# SCH_Copy_of_car_SchDoc_2023-05-21.net
KiCad netlist of a schematic drawn in EasyEDA
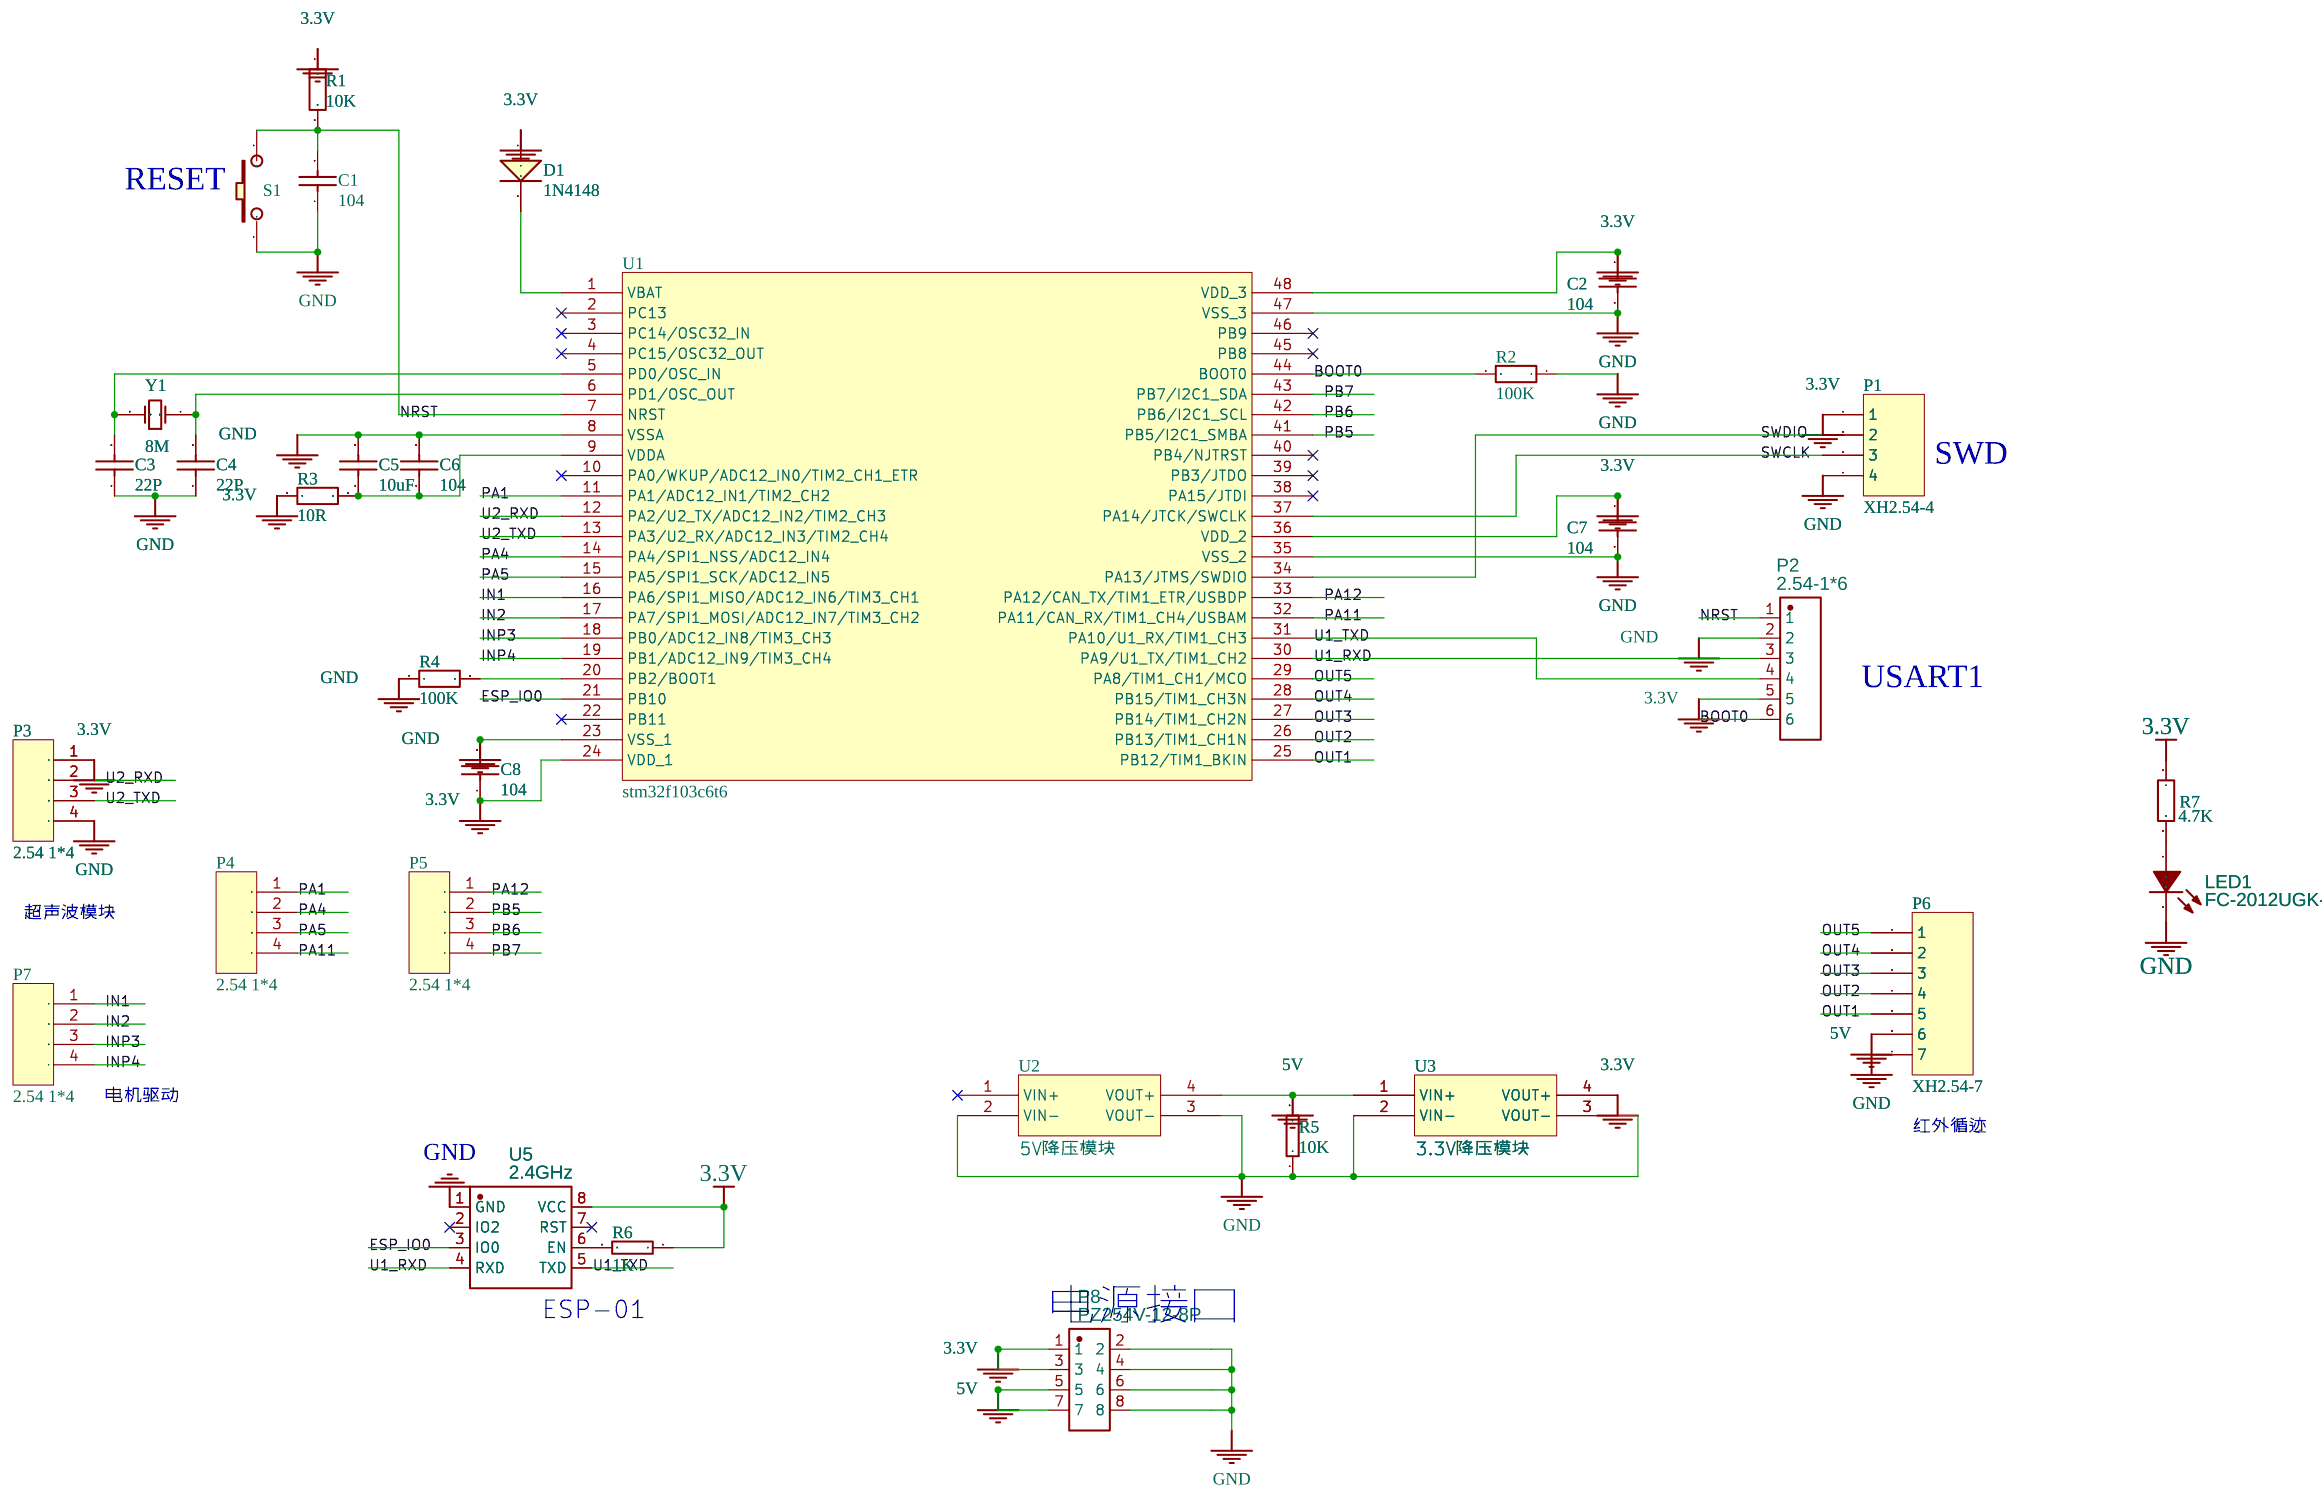
[diagram p0: schematic sheet]

(export (version "E")
  (design (tool "Eeschema 10.0.6"))
  (components
    (comp (ref "C1") (value "104") (libsource (lib "") (part "Unknown_210_-825")))
    (comp (ref "C2") (value "104") (libsource (lib "") (part "Unknown_830_-785")))
    (comp (ref "C3") (value "22P") (libsource (lib "") (part "Unknown_110_-685")))
    (comp (ref "C4") (value "22P") (libsource (lib "") (part "Unknown_150_-685")))
    (comp (ref "C5") (value "10uF") (libsource (lib "") (part "Unknown_230_-685")))
    (comp (ref "C6") (value "104") (libsource (lib "") (part "Unknown_260_-685")))
    (comp (ref "C7") (value "104") (libsource (lib "") (part "Unknown_830_-665")))
    (comp (ref "C8") (value "104") (libsource (lib "") (part "Unknown_290_-535")))
    (comp (ref "D1") (value "1N4148") (libsource (lib "") (part "Unknown_300_-815")))
    (comp (ref "LED1")
      (value "FC-2012UGK-520D5")
      (fields (field (name "BOM_Manufacturer Part") "NCD0805G1") (field (name "BOM_Supplier Part") "C84260"))
      (libsource (lib "") (part "FC-2012UGK-520D5"))
    )
    (comp (ref "P1") (value "XH2.54-4") (libsource (lib "") (part "Unknown_961_-725")))
    (comp (ref "P2")
      (value "2.54-1*6")
      (fields (field (name "BOM_Supplier Part") "C5156615"))
      (libsource (lib "") (part "2.54-1*6"))
    )
    (comp (ref "P3") (value "2.54 1*4") (libsource (lib "") (part "Unknown_50_-555")))
    (comp (ref "P4") (value "2.54 1*4") (libsource (lib "") (part "Unknown_150_-490")))
    (comp (ref "P5") (value "2.54 1*4") (libsource (lib "") (part "Unknown_245_-490")))
    (comp (ref "P6") (value "XH2.54-7") (libsource (lib "") (part "Unknown_985_-470")))
    (comp (ref "P7") (value "2.54 1*4") (libsource (lib "") (part "Unknown_50_-435")))
    (comp (ref "P8")
      (value "PZ254V-12-8P")
      (fields (field (name "BOM_Supplier Part") "C492421"))
      (libsource (lib "") (part "PZ254V-12-8P"))
    )
    (comp (ref "R1") (value "10K") (libsource (lib "") (part "Unknown_200_-855")))
    (comp (ref "R2") (value "100K") (libsource (lib "") (part "Unknown_800_-745")))
    (comp (ref "R3") (value "10R") (libsource (lib "") (part "Unknown_220_-675")))
    (comp (ref "R4") (value "100K") (libsource (lib "") (part "Unknown_250_-575")))
    (comp (ref "R5") (value "10K") (libsource (lib "") (part "Unknown_680_-380")))
    (comp (ref "R6") (value "1K") (libsource (lib "") (part "Unknown_335_-305")))
    (comp (ref "R7") (value "4.7K") (libsource (lib "") (part "Unknown_1100_-535")))
    (comp (ref "S1") (value "key") (libsource (lib "") (part "Unknown_170_-795")))
    (comp (ref "U1") (value "stm32f103c6t6") (libsource (lib "") (part "Unknown_350_-785")))
    (comp (ref "U2") (value "5V降压模块") (libsource (lib "") (part "Unknown_545_-390")))
    (comp (ref "U3") (value "3.3V降压模块") (libsource (lib "") (part "Unknown_740_-390")))
    (comp (ref "U5")
      (value "2.4GHz")
      (fields (field (name "BOM_Manufacturer Part") "ESP-01") (field (name "BOM_Supplier Part") "C503581"))
      (libsource (lib "") (part "ESP-01"))
    )
    (comp (ref "Y1") (value "8M") (libsource (lib "") (part "Unknown_100_-715")))
  )
  (nets
    (net (code "1") (name "/BOOT0") (class "Default")
      (node (ref "P2") (pin "6") (pinfunction "6_6") (pintype "unspecified"))
      (node (ref "R2") (pin "2") (pinfunction "2_2") (pintype "unspecified"))
      (node (ref "U1") (pin "44") (pinfunction "BOOT0_44") (pintype "unspecified"))
    )
    (net (code "2") (name "/ESP_IO0") (class "Default")
      (node (ref "U1") (pin "21") (pinfunction "PB10_21") (pintype "unspecified"))
      (node (ref "U5") (pin "3") (pinfunction "IO0_3") (pintype "unspecified"))
    )
    (net (code "3") (name "/IN1") (class "Default")
      (node (ref "P7") (pin "1") (pinfunction "1_1") (pintype "unspecified"))
      (node (ref "U1") (pin "16") (pinfunction "PA6/SPI1_MISO/ADC12_IN6/TIM3_CH1_16") (pintype "unspecified"))
    )
    (net (code "4") (name "/IN2") (class "Default")
      (node (ref "P7") (pin "2") (pinfunction "2_2") (pintype "unspecified"))
      (node (ref "U1") (pin "17") (pinfunction "PA7/SPI1_MOSI/ADC12_IN7/TIM3_CH2_17") (pintype "unspecified"))
    )
    (net (code "5") (name "/INP3") (class "Default")
      (node (ref "P7") (pin "3") (pinfunction "3_3") (pintype "unspecified"))
      (node (ref "U1") (pin "18") (pinfunction "PB0/ADC12_IN8/TIM3_CH3_18") (pintype "unspecified"))
    )
    (net (code "6") (name "/INP4") (class "Default")
      (node (ref "P7") (pin "4") (pinfunction "4_4") (pintype "unspecified"))
      (node (ref "U1") (pin "19") (pinfunction "PB1/ADC12_IN9/TIM3_CH4_19") (pintype "unspecified"))
    )
    (net (code "7") (name "/NRST") (class "Default")
      (node (ref "C1") (pin "2") (pintype "unspecified"))
      (node (ref "P2") (pin "1") (pinfunction "1_1") (pintype "unspecified"))
      (node (ref "R1") (pin "2") (pinfunction "2_2") (pintype "unspecified"))
      (node (ref "S1") (pin "2") (pinfunction "2_2") (pintype "unspecified"))
      (node (ref "U1") (pin "7") (pinfunction "NRST_7") (pintype "unspecified"))
    )
    (net (code "8") (name "/OUT1") (class "Default")
      (node (ref "P6") (pin "5") (pinfunction "5_5") (pintype "unspecified"))
      (node (ref "U1") (pin "25") (pinfunction "PB12/TIM1_BKIN_25") (pintype "unspecified"))
    )
    (net (code "9") (name "/OUT2") (class "Default")
      (node (ref "P6") (pin "4") (pinfunction "4_4") (pintype "unspecified"))
      (node (ref "U1") (pin "26") (pinfunction "PB13/TIM1_CH1N_26") (pintype "unspecified"))
    )
    (net (code "10") (name "/OUT3") (class "Default")
      (node (ref "P6") (pin "3") (pinfunction "3_3") (pintype "unspecified"))
      (node (ref "U1") (pin "27") (pinfunction "PB14/TIM1_CH2N_27") (pintype "unspecified"))
    )
    (net (code "11") (name "/OUT4") (class "Default")
      (node (ref "P6") (pin "2") (pinfunction "2_2") (pintype "unspecified"))
      (node (ref "U1") (pin "28") (pinfunction "PB15/TIM1_CH3N_28") (pintype "unspecified"))
    )
    (net (code "12") (name "/OUT5") (class "Default")
      (node (ref "P6") (pin "1") (pinfunction "1_1") (pintype "unspecified"))
      (node (ref "U1") (pin "29") (pinfunction "PA8/TIM1_CH1/MCO_29") (pintype "unspecified"))
    )
    (net (code "13") (name "/PA1") (class "Default")
      (node (ref "P4") (pin "1") (pinfunction "1_1") (pintype "unspecified"))
      (node (ref "U1") (pin "11") (pinfunction "PA1/ADC12_IN1/TIM2_CH2_11") (pintype "unspecified"))
    )
    (net (code "14") (name "/PA4") (class "Default")
      (node (ref "P4") (pin "2") (pinfunction "2_2") (pintype "unspecified"))
      (node (ref "U1") (pin "14") (pinfunction "PA4/SPI1_NSS/ADC12_IN4_14") (pintype "unspecified"))
    )
    (net (code "15") (name "/PA5") (class "Default")
      (node (ref "P4") (pin "3") (pinfunction "3_3") (pintype "unspecified"))
      (node (ref "U1") (pin "15") (pinfunction "PA5/SPI1_SCK/ADC12_IN5_15") (pintype "unspecified"))
    )
    (net (code "16") (name "/PA11") (class "Default")
      (node (ref "P4") (pin "4") (pinfunction "4_4") (pintype "unspecified"))
      (node (ref "U1") (pin "32") (pinfunction "PA11/CAN_RX/TIM1_CH4/USBAM_32") (pintype "unspecified"))
    )
    (net (code "17") (name "/PA12") (class "Default")
      (node (ref "P5") (pin "1") (pinfunction "1_1") (pintype "unspecified"))
      (node (ref "U1") (pin "33") (pinfunction "PA12/CAN_TX/TIM1_ETR/USBDP_33") (pintype "unspecified"))
    )
    (net (code "18") (name "/PB5") (class "Default")
      (node (ref "P5") (pin "2") (pinfunction "2_2") (pintype "unspecified"))
      (node (ref "U1") (pin "41") (pinfunction "PB5/I2C1_SMBA_41") (pintype "unspecified"))
    )
    (net (code "19") (name "/PB6") (class "Default")
      (node (ref "P5") (pin "3") (pinfunction "3_3") (pintype "unspecified"))
      (node (ref "U1") (pin "42") (pinfunction "PB6/I2C1_SCL_42") (pintype "unspecified"))
    )
    (net (code "20") (name "/PB7") (class "Default")
      (node (ref "P5") (pin "4") (pinfunction "4_4") (pintype "unspecified"))
      (node (ref "U1") (pin "43") (pinfunction "PB7/I2C1_SDA_43") (pintype "unspecified"))
    )
    (net (code "21") (name "/SWCLK") (class "Default")
      (node (ref "P1") (pin "3") (pinfunction "3_3") (pintype "unspecified"))
      (node (ref "U1") (pin "37") (pinfunction "PA14/JTCK/SWCLK_37") (pintype "unspecified"))
    )
    (net (code "22") (name "/SWDIO") (class "Default")
      (node (ref "P1") (pin "2") (pinfunction "2_2") (pintype "unspecified"))
      (node (ref "U1") (pin "34") (pinfunction "PA13/JTMS/SWDIO_34") (pintype "unspecified"))
    )
    (net (code "23") (name "/U1_RXD") (class "Default")
      (node (ref "P2") (pin "3") (pinfunction "3_3") (pintype "unspecified"))
      (node (ref "U1") (pin "30") (pinfunction "PA9/U1_TX/TIM1_CH2_30") (pintype "unspecified"))
      (node (ref "U5") (pin "4") (pinfunction "RXD_4") (pintype "unspecified"))
    )
    (net (code "24") (name "/U1_TXD") (class "Default")
      (node (ref "P2") (pin "4") (pinfunction "4_4") (pintype "unspecified"))
      (node (ref "U1") (pin "31") (pinfunction "PA10/U1_RX/TIM1_CH3_31") (pintype "unspecified"))
      (node (ref "U5") (pin "5") (pinfunction "TXD_5") (pintype "unspecified"))
    )
    (net (code "25") (name "/U2_RXD") (class "Default")
      (node (ref "P3") (pin "2") (pinfunction "2_2") (pintype "unspecified"))
      (node (ref "U1") (pin "12") (pinfunction "PA2/U2_TX/ADC12_IN2/TIM2_CH3_12") (pintype "unspecified"))
    )
    (net (code "26") (name "/U2_TXD") (class "Default")
      (node (ref "P3") (pin "3") (pinfunction "3_3") (pintype "unspecified"))
      (node (ref "U1") (pin "13") (pinfunction "PA3/U2_RX/ADC12_IN3/TIM2_CH4_13") (pintype "unspecified"))
    )
    (net (code "27") (name "3.3V") (class "Default")
      (node (ref "C2") (pin "1") (pintype "unspecified"))
      (node (ref "C7") (pin "1") (pintype "unspecified"))
      (node (ref "C8") (pin "1") (pintype "unspecified"))
      (node (ref "D1") (pin "1") (pinfunction "A_1") (pintype "unspecified"))
      (node (ref "P1") (pin "1") (pinfunction "1_1") (pintype "unspecified"))
      (node (ref "P2") (pin "5") (pinfunction "5_5") (pintype "unspecified"))
      (node (ref "P3") (pin "1") (pinfunction "1_1") (pintype "unspecified"))
      (node (ref "P8") (pin "1") (pinfunction "1_1") (pintype "unspecified"))
      (node (ref "P8") (pin "3") (pinfunction "3_3") (pintype "unspecified"))
      (node (ref "R1") (pin "1") (pinfunction "1_1") (pintype "unspecified"))
      (node (ref "R3") (pin "1") (pinfunction "1_1") (pintype "unspecified"))
      (node (ref "R6") (pin "1") (pinfunction "1_1") (pintype "unspecified"))
      (node (ref "R7") (pin "1") (pinfunction "1_1") (pintype "unspecified"))
      (node (ref "U1") (pin "24") (pinfunction "VDD_1_24") (pintype "unspecified"))
      (node (ref "U1") (pin "36") (pinfunction "VDD_2_36") (pintype "unspecified"))
      (node (ref "U1") (pin "48") (pinfunction "VDD_3_48") (pintype "unspecified"))
      (node (ref "U3") (pin "4") (pinfunction "VOUT+_4") (pintype "unspecified"))
      (node (ref "U5") (pin "8") (pinfunction "VCC_8") (pintype "unspecified"))
    )
    (net (code "28") (name "5V") (class "Default")
      (node (ref "P6") (pin "6") (pinfunction "6_6") (pintype "unspecified"))
      (node (ref "P8") (pin "5") (pinfunction "5_5") (pintype "unspecified"))
      (node (ref "P8") (pin "7") (pinfunction "7_7") (pintype "unspecified"))
      (node (ref "R5") (pin "2") (pinfunction "2_2") (pintype "unspecified"))
      (node (ref "U2") (pin "4") (pinfunction "VOUT+_4") (pintype "unspecified"))
      (node (ref "U3") (pin "1") (pinfunction "VIN+_1") (pintype "unspecified"))
    )
    (net (code "29") (name "GND") (class "Default")
      (node (ref "C1") (pin "1") (pintype "unspecified"))
      (node (ref "C2") (pin "2") (pintype "unspecified"))
      (node (ref "C3") (pin "1") (pintype "unspecified"))
      (node (ref "C4") (pin "1") (pintype "unspecified"))
      (node (ref "C5") (pin "2") (pintype "unspecified"))
      (node (ref "C6") (pin "2") (pintype "unspecified"))
      (node (ref "C7") (pin "2") (pintype "unspecified"))
      (node (ref "C8") (pin "2") (pintype "unspecified"))
      (node (ref "LED1") (pin "2") (pinfunction "K_2") (pintype "unspecified"))
      (node (ref "P1") (pin "4") (pinfunction "4_4") (pintype "unspecified"))
      (node (ref "P2") (pin "2") (pinfunction "2_2") (pintype "unspecified"))
      (node (ref "P3") (pin "4") (pinfunction "4_4") (pintype "unspecified"))
      (node (ref "P6") (pin "7") (pinfunction "7_7") (pintype "unspecified"))
      (node (ref "P8") (pin "2") (pinfunction "2_2") (pintype "unspecified"))
      (node (ref "P8") (pin "4") (pinfunction "4_4") (pintype "unspecified"))
      (node (ref "P8") (pin "6") (pinfunction "6_6") (pintype "unspecified"))
      (node (ref "P8") (pin "8") (pinfunction "8_8") (pintype "unspecified"))
      (node (ref "R2") (pin "1") (pinfunction "1_1") (pintype "unspecified"))
      (node (ref "R4") (pin "1") (pinfunction "1_1") (pintype "unspecified"))
      (node (ref "R5") (pin "1") (pinfunction "1_1") (pintype "unspecified"))
      (node (ref "S1") (pin "1") (pinfunction "1_1") (pintype "unspecified"))
      (node (ref "U1") (pin "23") (pinfunction "VSS_1_23") (pintype "unspecified"))
      (node (ref "U1") (pin "35") (pinfunction "VSS_2_35") (pintype "unspecified"))
      (node (ref "U1") (pin "47") (pinfunction "VSS_3_47") (pintype "unspecified"))
      (node (ref "U1") (pin "8") (pinfunction "VSSA_8") (pintype "unspecified"))
      (node (ref "U2") (pin "2") (pinfunction "VIN-_2") (pintype "unspecified"))
      (node (ref "U2") (pin "3") (pinfunction "VOUT-_3") (pintype "unspecified"))
      (node (ref "U3") (pin "2") (pinfunction "VIN-_2") (pintype "unspecified"))
      (node (ref "U3") (pin "3") (pinfunction "VOUT-_3") (pintype "unspecified"))
      (node (ref "U5") (pin "1") (pinfunction "GND_1") (pintype "unspecified"))
    )
    (net (code "30") (name "Net-(D1-K)") (class "Default")
      (node (ref "D1") (pin "2") (pinfunction "K_2") (pintype "unspecified"))
      (node (ref "U1") (pin "1") (pinfunction "VBAT_1") (pintype "unspecified"))
    )
    (net (code "31") (name "Net-(LED1-A)") (class "Default")
      (node (ref "LED1") (pin "1") (pinfunction "A_1") (pintype "unspecified"))
      (node (ref "R7") (pin "2") (pinfunction "2_2") (pintype "unspecified"))
    )
    (net (code "32") (name "Net-(U1-PB2{slash}BOOT1)") (class "Default")
      (node (ref "R4") (pin "2") (pinfunction "2_2") (pintype "unspecified"))
      (node (ref "U1") (pin "20") (pinfunction "PB2/BOOT1_20") (pintype "unspecified"))
    )
    (net (code "33") (name "Net-(U1-PD0{slash}OSC_IN)") (class "Default")
      (node (ref "C3") (pin "2") (pintype "unspecified"))
      (node (ref "U1") (pin "5") (pinfunction "PD0/OSC_IN_5") (pintype "unspecified"))
      (node (ref "Y1") (pin "2") (pinfunction "OSC2_2") (pintype "unspecified"))
    )
    (net (code "34") (name "Net-(U1-PD1{slash}OSC_OUT)") (class "Default")
      (node (ref "C4") (pin "2") (pintype "unspecified"))
      (node (ref "U1") (pin "6") (pinfunction "PD1/OSC_OUT_6") (pintype "unspecified"))
      (node (ref "Y1") (pin "1") (pinfunction "OSC1_1") (pintype "unspecified"))
    )
    (net (code "35") (name "Net-(U1-VDDA)") (class "Default")
      (node (ref "C5") (pin "1") (pintype "unspecified"))
      (node (ref "C6") (pin "1") (pintype "unspecified"))
      (node (ref "R3") (pin "2") (pinfunction "2_2") (pintype "unspecified"))
      (node (ref "U1") (pin "9") (pinfunction "VDDA_9") (pintype "unspecified"))
    )
    (net (code "36") (name "Net-(U5-EN)") (class "Default")
      (node (ref "R6") (pin "2") (pinfunction "2_2") (pintype "unspecified"))
      (node (ref "U5") (pin "6") (pinfunction "EN_6") (pintype "unspecified"))
    )
    (net (code "37") (name "unconnected-(U1-PA0{slash}WKUP{slash}ADC12_IN0{slash}TIM2_CH1_ETR-Pad10)") (class "Default")
      (node (ref "U1") (pin "10") (pinfunction "PA0/WKUP/ADC12_IN0/TIM2_CH1_ETR_10") (pintype "unspecified+no_connect"))
    )
    (net (code "38") (name "unconnected-(U1-PA15{slash}JTDI-Pad38)") (class "Default")
      (node (ref "U1") (pin "38") (pinfunction "PA15/JTDI_38") (pintype "unspecified+no_connect"))
    )
    (net (code "39") (name "unconnected-(U1-PB3{slash}JTDO-Pad39)") (class "Default")
      (node (ref "U1") (pin "39") (pinfunction "PB3/JTDO_39") (pintype "unspecified+no_connect"))
    )
    (net (code "40") (name "unconnected-(U1-PB4{slash}NJTRST-Pad40)") (class "Default")
      (node (ref "U1") (pin "40") (pinfunction "PB4/NJTRST_40") (pintype "unspecified+no_connect"))
    )
    (net (code "41") (name "unconnected-(U1-PB8-Pad45)") (class "Default")
      (node (ref "U1") (pin "45") (pinfunction "PB8_45") (pintype "unspecified+no_connect"))
    )
    (net (code "42") (name "unconnected-(U1-PB9-Pad46)") (class "Default")
      (node (ref "U1") (pin "46") (pinfunction "PB9_46") (pintype "unspecified+no_connect"))
    )
    (net (code "43") (name "unconnected-(U1-PB11-Pad22)") (class "Default")
      (node (ref "U1") (pin "22") (pinfunction "PB11_22") (pintype "unspecified+no_connect"))
    )
    (net (code "44") (name "unconnected-(U1-PC13-Pad2)") (class "Default")
      (node (ref "U1") (pin "2") (pinfunction "PC13_2") (pintype "unspecified+no_connect"))
    )
    (net (code "45") (name "unconnected-(U1-PC14{slash}OSC32_IN-Pad3)") (class "Default")
      (node (ref "U1") (pin "3") (pinfunction "PC14/OSC32_IN_3") (pintype "unspecified+no_connect"))
    )
    (net (code "46") (name "unconnected-(U1-PC15{slash}OSC32_OUT-Pad4)") (class "Default")
      (node (ref "U1") (pin "4") (pinfunction "PC15/OSC32_OUT_4") (pintype "unspecified+no_connect"))
    )
    (net (code "47") (name "unconnected-(U2-VIN+-Pad1)") (class "Default")
      (node (ref "U2") (pin "1") (pinfunction "VIN+_1") (pintype "unspecified+no_connect"))
    )
    (net (code "48") (name "unconnected-(U5-IO2-Pad2)") (class "Default")
      (node (ref "U5") (pin "2") (pinfunction "IO2_2") (pintype "unspecified+no_connect"))
    )
    (net (code "49") (name "unconnected-(U5-RST-Pad7)") (class "Default")
      (node (ref "U5") (pin "7") (pinfunction "RST_7") (pintype "unspecified+no_connect"))
    )
  )
)
